# tetris_mega.net
KiCad netlist of a schematic drawn in EAGLE
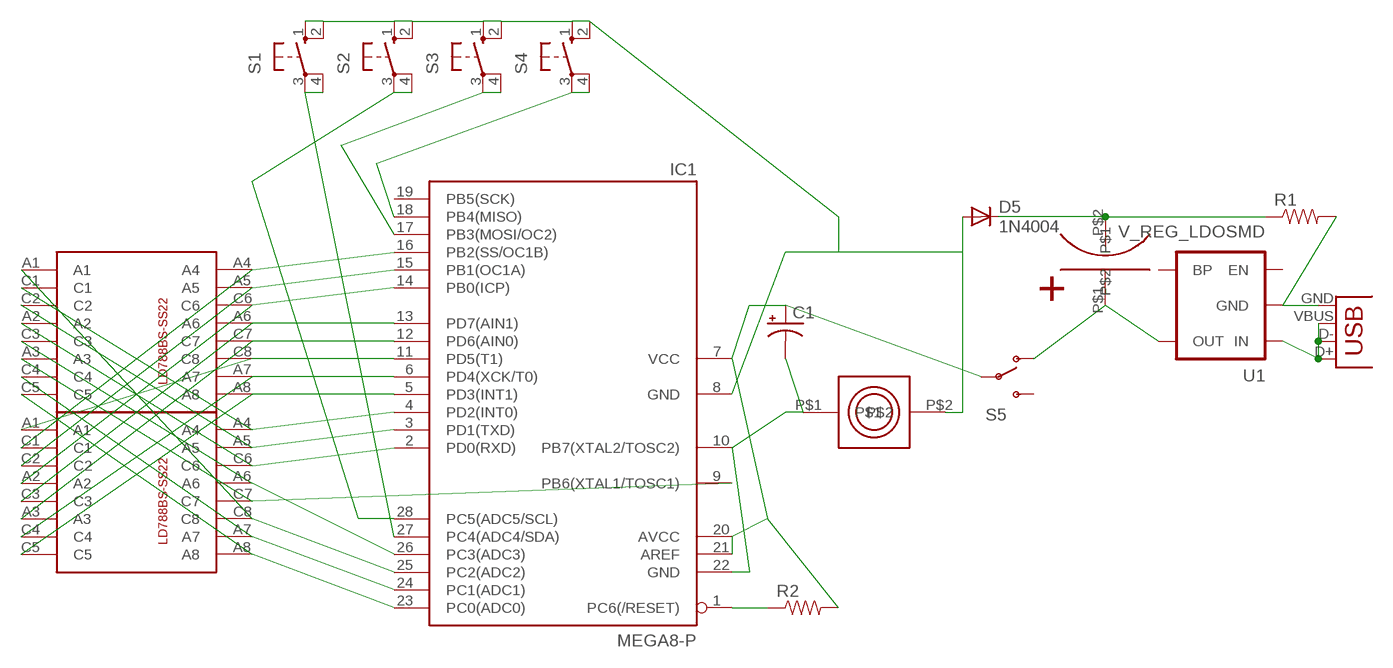
[diagram p0: schematic, sheet 1]

(export (version "E")
  (design (tool "Eeschema 10.0.6"))
  (components
    (comp (ref "C1")
      (value "CAP_POLPTH1")
      (footprint "eagle-import:CPOL-RADIAL-100UF-25V")
      (libsource (lib "eagle-import") (part "CAP_POLPTH1"))
    )
    (comp (ref "D5")
      (value "1N4004")
      (footprint "eagle-import:DO41-10")
      (libsource (lib "eagle-import") (part "1N4004"))
    )
    (comp (ref "IC1")
      (value "MEGA8-P")
      (footprint "eagle-import:DIL28-3")
      (libsource (lib "eagle-import") (part "MEGA8-P"))
    )
    (comp (ref "R1")
      (value "RESISTORPTH1")
      (footprint "eagle-import:AXIAL-0.3")
      (libsource (lib "eagle-import") (part "RESISTORPTH1"))
    )
    (comp (ref "R2")
      (value "RESISTORPTH1")
      (footprint "eagle-import:AXIAL-0.3")
      (libsource (lib "eagle-import") (part "RESISTORPTH1"))
    )
    (comp (ref "S1")
      (value "10-XX")
      (footprint "eagle-import:B3F-10XX")
      (fields (field (name "MPN") "B3F-1000"))
      (libsource (lib "eagle-import") (part "10-XX"))
    )
    (comp (ref "S2")
      (value "10-XX")
      (footprint "eagle-import:B3F-10XX")
      (fields (field (name "MPN") "B3F-1000"))
      (libsource (lib "eagle-import") (part "10-XX"))
    )
    (comp (ref "S3")
      (value "10-XX")
      (footprint "eagle-import:B3F-10XX")
      (fields (field (name "MPN") "B3F-1000"))
      (libsource (lib "eagle-import") (part "10-XX"))
    )
    (comp (ref "S4")
      (value "10-XX")
      (footprint "eagle-import:B3F-10XX")
      (fields (field (name "MPN") "B3F-1000"))
      (libsource (lib "eagle-import") (part "10-XX"))
    )
    (comp (ref "S5")
      (value "SWITCH-SPSTSMD2")
      (footprint "eagle-import:SWITCH-SPDT-SMD")
      (libsource (lib "eagle-import") (part "SWITCH-SPSTSMD2"))
    )
    (comp (ref "U$1")
      (value "LD788BS-SS22")
      (footprint "eagle-import:LD788BS-SS22")
      (libsource (lib "eagle-import") (part "LD788BS-SS22"))
    )
    (comp (ref "U$2")
      (value "LD788BS-SS22")
      (footprint "eagle-import:LD788BS-SS22")
      (libsource (lib "eagle-import") (part "LD788BS-SS22"))
    )
    (comp (ref "U$4")
      (value "I-80450RF")
      (footprint "eagle-import:ISK4.1K_I-80450RF_I2G")
      (libsource (lib "eagle-import") (part "I-80450RF"))
    )
    (comp (ref "U$5")
      (value "NICHICON_12F")
      (footprint "eagle-import:NICHICON_10X30")
      (libsource (lib "eagle-import") (part "NICHICON_12F"))
    )
    (comp (ref "U1")
      (value "V_REG_LDOSMD")
      (footprint "eagle-import:SOT23-5")
      (libsource (lib "eagle-import") (part "V_REG_LDOSMD"))
    )
    (comp (ref "X1")
      (value "USB-MICROB")
      (footprint "eagle-import:USB-MICROB")
      (libsource (lib "eagle-import") (part "USB-MICROB"))
    )
  )
  (nets
    (net (code "1") (name "Net-(C1-+)") (class "Default")
      (node (ref "C1") (pin "1") (pinfunction "+_1") (pintype "passive"))
      (node (ref "IC1") (pin "20") (pinfunction "AVCC_20") (pintype "power_in"))
      (node (ref "IC1") (pin "21") (pinfunction "AREF_21") (pintype "passive"))
      (node (ref "IC1") (pin "7") (pinfunction "VCC_7") (pintype "power_in"))
      (node (ref "R2") (pin "P$2") (pinfunction "2_P$2") (pintype "passive"))
      (node (ref "S5") (pin "2") (pinfunction "P_2") (pintype "passive"))
    )
    (net (code "2") (name "Net-(C1--)") (class "Default")
      (node (ref "C1") (pin "2") (pinfunction "-_2") (pintype "passive"))
      (node (ref "IC1") (pin "10") (pinfunction "PB7(XTAL2/TOSC2)_10") (pintype "bidirectional"))
      (node (ref "IC1") (pin "22") (pinfunction "GND_22") (pintype "power_in"))
      (node (ref "U$4") (pin "P$1") (pinfunction "P$1_P$1") (pintype "bidirectional"))
    )
    (net (code "3") (name "Net-(IC1-PB0(ICP))") (class "Default")
      (node (ref "IC1") (pin "14") (pinfunction "PB0(ICP)_14") (pintype "bidirectional"))
      (node (ref "U$1") (pin "A2") (pinfunction "A2_A2") (pintype "bidirectional"))
      (node (ref "U$2") (pin "C6") (pinfunction "C6_C6") (pintype "bidirectional"))
    )
    (net (code "4") (name "Net-(IC1-PB1(OC1A))") (class "Default")
      (node (ref "IC1") (pin "15") (pinfunction "PB1(OC1A)_15") (pintype "bidirectional"))
      (node (ref "U$1") (pin "C2") (pinfunction "C2_C2") (pintype "bidirectional"))
      (node (ref "U$2") (pin "A5") (pinfunction "A5_A5") (pintype "bidirectional"))
    )
    (net (code "5") (name "Net-(IC1-PB2(SS{slash}OC1B))") (class "Default")
      (node (ref "IC1") (pin "16") (pinfunction "PB2(SS/OC1B)_16") (pintype "bidirectional"))
      (node (ref "U$1") (pin "C1") (pinfunction "C1_C1") (pintype "bidirectional"))
      (node (ref "U$2") (pin "A4") (pinfunction "A4_A4") (pintype "bidirectional"))
    )
    (net (code "6") (name "Net-(IC1-PB3(MOSI{slash}OC2))") (class "Default")
      (node (ref "IC1") (pin "17") (pinfunction "PB3(MOSI/OC2)_17") (pintype "bidirectional"))
      (node (ref "S3") (pin "3") (pinfunction "P_3") (pintype "passive"))
      (node (ref "S3") (pin "4") (pinfunction "P1_4") (pintype "passive"))
    )
    (net (code "7") (name "Net-(IC1-PB4(MISO))") (class "Default")
      (node (ref "IC1") (pin "18") (pinfunction "PB4(MISO)_18") (pintype "bidirectional"))
      (node (ref "S4") (pin "3") (pinfunction "P_3") (pintype "passive"))
      (node (ref "S4") (pin "4") (pinfunction "P1_4") (pintype "passive"))
    )
    (net (code "8") (name "Net-(IC1-PB6(XTAL1{slash}TOSC1))") (class "Default")
      (node (ref "IC1") (pin "9") (pinfunction "PB6(XTAL1/TOSC1)_9") (pintype "bidirectional"))
      (node (ref "U$1") (pin "C7") (pinfunction "C7_C7") (pintype "bidirectional"))
      (node (ref "U$2") (pin "A3") (pinfunction "A3_A3") (pintype "bidirectional"))
    )
    (net (code "9") (name "Net-(IC1-PC0(ADC0))") (class "Default")
      (node (ref "IC1") (pin "23") (pinfunction "PC0(ADC0)_23") (pintype "bidirectional"))
      (node (ref "U$1") (pin "A8") (pinfunction "A8_A8") (pintype "bidirectional"))
      (node (ref "U$2") (pin "C5") (pinfunction "C5_C5") (pintype "bidirectional"))
    )
    (net (code "10") (name "Net-(IC1-PC1(ADC1))") (class "Default")
      (node (ref "IC1") (pin "24") (pinfunction "PC1(ADC1)_24") (pintype "bidirectional"))
      (node (ref "U$1") (pin "A7") (pinfunction "A7_A7") (pintype "bidirectional"))
      (node (ref "U$2") (pin "C4") (pinfunction "C4_C4") (pintype "bidirectional"))
    )
    (net (code "11") (name "Net-(IC1-PC2(ADC2))") (class "Default")
      (node (ref "IC1") (pin "25") (pinfunction "PC2(ADC2)_25") (pintype "bidirectional"))
      (node (ref "U$1") (pin "C8") (pinfunction "C8_C8") (pintype "bidirectional"))
      (node (ref "U$2") (pin "A1") (pinfunction "A1_A1") (pintype "bidirectional"))
    )
    (net (code "12") (name "Net-(IC1-PC3(ADC3))") (class "Default")
      (node (ref "IC1") (pin "26") (pinfunction "PC3(ADC3)_26") (pintype "bidirectional"))
      (node (ref "U$1") (pin "A6") (pinfunction "A6_A6") (pintype "bidirectional"))
      (node (ref "U$2") (pin "C3") (pinfunction "C3_C3") (pintype "bidirectional"))
    )
    (net (code "13") (name "Net-(IC1-PC4(ADC4{slash}SDA))") (class "Default")
      (node (ref "IC1") (pin "27") (pinfunction "PC4(ADC4/SDA)_27") (pintype "bidirectional"))
      (node (ref "S1") (pin "3") (pinfunction "P_3") (pintype "passive"))
      (node (ref "S1") (pin "4") (pinfunction "P1_4") (pintype "passive"))
    )
    (net (code "14") (name "Net-(IC1-PC5(ADC5{slash}SCL))") (class "Default")
      (node (ref "IC1") (pin "28") (pinfunction "PC5(ADC5/SCL)_28") (pintype "bidirectional"))
      (node (ref "S2") (pin "3") (pinfunction "P_3") (pintype "passive"))
      (node (ref "S2") (pin "4") (pinfunction "P1_4") (pintype "passive"))
    )
    (net (code "15") (name "Net-(IC1-PC6({slash}RESET))") (class "Default")
      (node (ref "IC1") (pin "1") (pinfunction "PC6(/RESET)_1") (pintype "bidirectional"))
      (node (ref "R2") (pin "P$1") (pinfunction "1_P$1") (pintype "passive"))
    )
    (net (code "16") (name "Net-(IC1-PD0(RXD))") (class "Default")
      (node (ref "IC1") (pin "2") (pinfunction "PD0(RXD)_2") (pintype "bidirectional"))
      (node (ref "U$1") (pin "C6") (pinfunction "C6_C6") (pintype "bidirectional"))
      (node (ref "U$2") (pin "A2") (pinfunction "A2_A2") (pintype "bidirectional"))
    )
    (net (code "17") (name "Net-(IC1-PD1(TXD))") (class "Default")
      (node (ref "IC1") (pin "3") (pinfunction "PD1(TXD)_3") (pintype "bidirectional"))
      (node (ref "U$1") (pin "A5") (pinfunction "A5_A5") (pintype "bidirectional"))
      (node (ref "U$2") (pin "C2") (pinfunction "C2_C2") (pintype "bidirectional"))
    )
    (net (code "18") (name "Net-(IC1-PD2(INT0))") (class "Default")
      (node (ref "IC1") (pin "4") (pinfunction "PD2(INT0)_4") (pintype "bidirectional"))
      (node (ref "U$1") (pin "A4") (pinfunction "A4_A4") (pintype "bidirectional"))
      (node (ref "U$2") (pin "C1") (pinfunction "C1_C1") (pintype "bidirectional"))
    )
    (net (code "19") (name "Net-(IC1-PD3(INT1))") (class "Default")
      (node (ref "IC1") (pin "5") (pinfunction "PD3(INT1)_5") (pintype "bidirectional"))
      (node (ref "U$1") (pin "C5") (pinfunction "C5_C5") (pintype "bidirectional"))
      (node (ref "U$2") (pin "A8") (pinfunction "A8_A8") (pintype "bidirectional"))
    )
    (net (code "20") (name "Net-(IC1-PD4(XCK{slash}T0))") (class "Default")
      (node (ref "IC1") (pin "6") (pinfunction "PD4(XCK/T0)_6") (pintype "bidirectional"))
      (node (ref "U$1") (pin "C4") (pinfunction "C4_C4") (pintype "bidirectional"))
      (node (ref "U$2") (pin "A7") (pinfunction "A7_A7") (pintype "bidirectional"))
    )
    (net (code "21") (name "Net-(IC1-PD5(T1))") (class "Default")
      (node (ref "IC1") (pin "11") (pinfunction "PD5(T1)_11") (pintype "bidirectional"))
      (node (ref "U$1") (pin "A1") (pinfunction "A1_A1") (pintype "bidirectional"))
      (node (ref "U$2") (pin "C8") (pinfunction "C8_C8") (pintype "bidirectional"))
    )
    (net (code "22") (name "Net-(IC1-PD6(AIN0))") (class "Default")
      (node (ref "IC1") (pin "12") (pinfunction "PD6(AIN0)_12") (pintype "bidirectional"))
      (node (ref "U$1") (pin "A3") (pinfunction "A3_A3") (pintype "bidirectional"))
      (node (ref "U$2") (pin "C7") (pinfunction "C7_C7") (pintype "bidirectional"))
    )
    (net (code "23") (name "Net-(IC1-PD7(AIN1))") (class "Default")
      (node (ref "IC1") (pin "13") (pinfunction "PD7(AIN1)_13") (pintype "bidirectional"))
      (node (ref "U$1") (pin "C3") (pinfunction "C3_C3") (pintype "bidirectional"))
      (node (ref "U$2") (pin "A6") (pinfunction "A6_A6") (pintype "bidirectional"))
    )
    (net (code "24") (name "Net-(R1-1)") (class "Default")
      (node (ref "D5") (pin "C") (pinfunction "C_C") (pintype "passive"))
      (node (ref "R1") (pin "P$1") (pinfunction "1_P$1") (pintype "passive"))
      (node (ref "U$5") (pin "P$2") (pinfunction "P$2_P$2") (pintype "bidirectional"))
    )
    (net (code "25") (name "Net-(R1-2)") (class "Default")
      (node (ref "R1") (pin "P$2") (pinfunction "2_P$2") (pintype "passive"))
      (node (ref "U1") (pin "2") (pinfunction "GND_2") (pintype "input"))
      (node (ref "X1") (pin "GND") (pinfunction "GND_GND") (pintype "bidirectional"))
    )
    (net (code "26") (name "Net-(S1-S)") (class "Default")
      (node (ref "D5") (pin "A") (pinfunction "A_A") (pintype "passive"))
      (node (ref "IC1") (pin "8") (pinfunction "GND_8") (pintype "power_in"))
      (node (ref "S1") (pin "1") (pinfunction "S_1") (pintype "passive"))
      (node (ref "S1") (pin "2") (pinfunction "S1_2") (pintype "passive"))
      (node (ref "S2") (pin "1") (pinfunction "S_1") (pintype "passive"))
      (node (ref "S2") (pin "2") (pinfunction "S1_2") (pintype "passive"))
      (node (ref "S3") (pin "1") (pinfunction "S_1") (pintype "passive"))
      (node (ref "S3") (pin "2") (pinfunction "S1_2") (pintype "passive"))
      (node (ref "S4") (pin "1") (pinfunction "S_1") (pintype "passive"))
      (node (ref "S4") (pin "2") (pinfunction "S1_2") (pintype "passive"))
      (node (ref "U$4") (pin "P$2") (pinfunction "P$2_P$2") (pintype "bidirectional"))
    )
    (net (code "27") (name "Net-(S5-O)") (class "Default")
      (node (ref "S5") (pin "1") (pinfunction "O_1") (pintype "passive"))
      (node (ref "U$5") (pin "P$1") (pinfunction "P$1_P$1") (pintype "bidirectional"))
      (node (ref "U1") (pin "5") (pinfunction "OUT_5") (pintype "passive"))
    )
    (net (code "28") (name "Net-(U1-IN)") (class "Default")
      (node (ref "U1") (pin "1") (pinfunction "IN_1") (pintype "input"))
      (node (ref "X1") (pin "D+") (pinfunction "D+_D+") (pintype "bidirectional"))
      (node (ref "X1") (pin "D-") (pinfunction "D-_D-") (pintype "bidirectional"))
      (node (ref "X1") (pin "VBUS") (pinfunction "VBUS_VBUS") (pintype "bidirectional"))
    )
    (net (code "29") (name "unconnected-(IC1-PB5(SCK)-Pad19)") (class "Default")
      (node (ref "IC1") (pin "19") (pinfunction "PB5(SCK)_19") (pintype "bidirectional"))
    )
    (net (code "30") (name "unconnected-(S5-S-Pad3)") (class "Default")
      (node (ref "S5") (pin "3") (pinfunction "S_3") (pintype "passive"))
    )
    (net (code "31") (name "unconnected-(U1-BP-Pad4)") (class "Default")
      (node (ref "U1") (pin "4") (pinfunction "BP_4") (pintype "input"))
    )
    (net (code "32") (name "unconnected-(U1-EN-Pad3)") (class "Default")
      (node (ref "U1") (pin "3") (pinfunction "EN_3") (pintype "input"))
    )
  )
)
